# SAMV71_Xplained_Ultra_MCU_Peripherals.net
KiCad netlist of a schematic drawn in Altium Designer
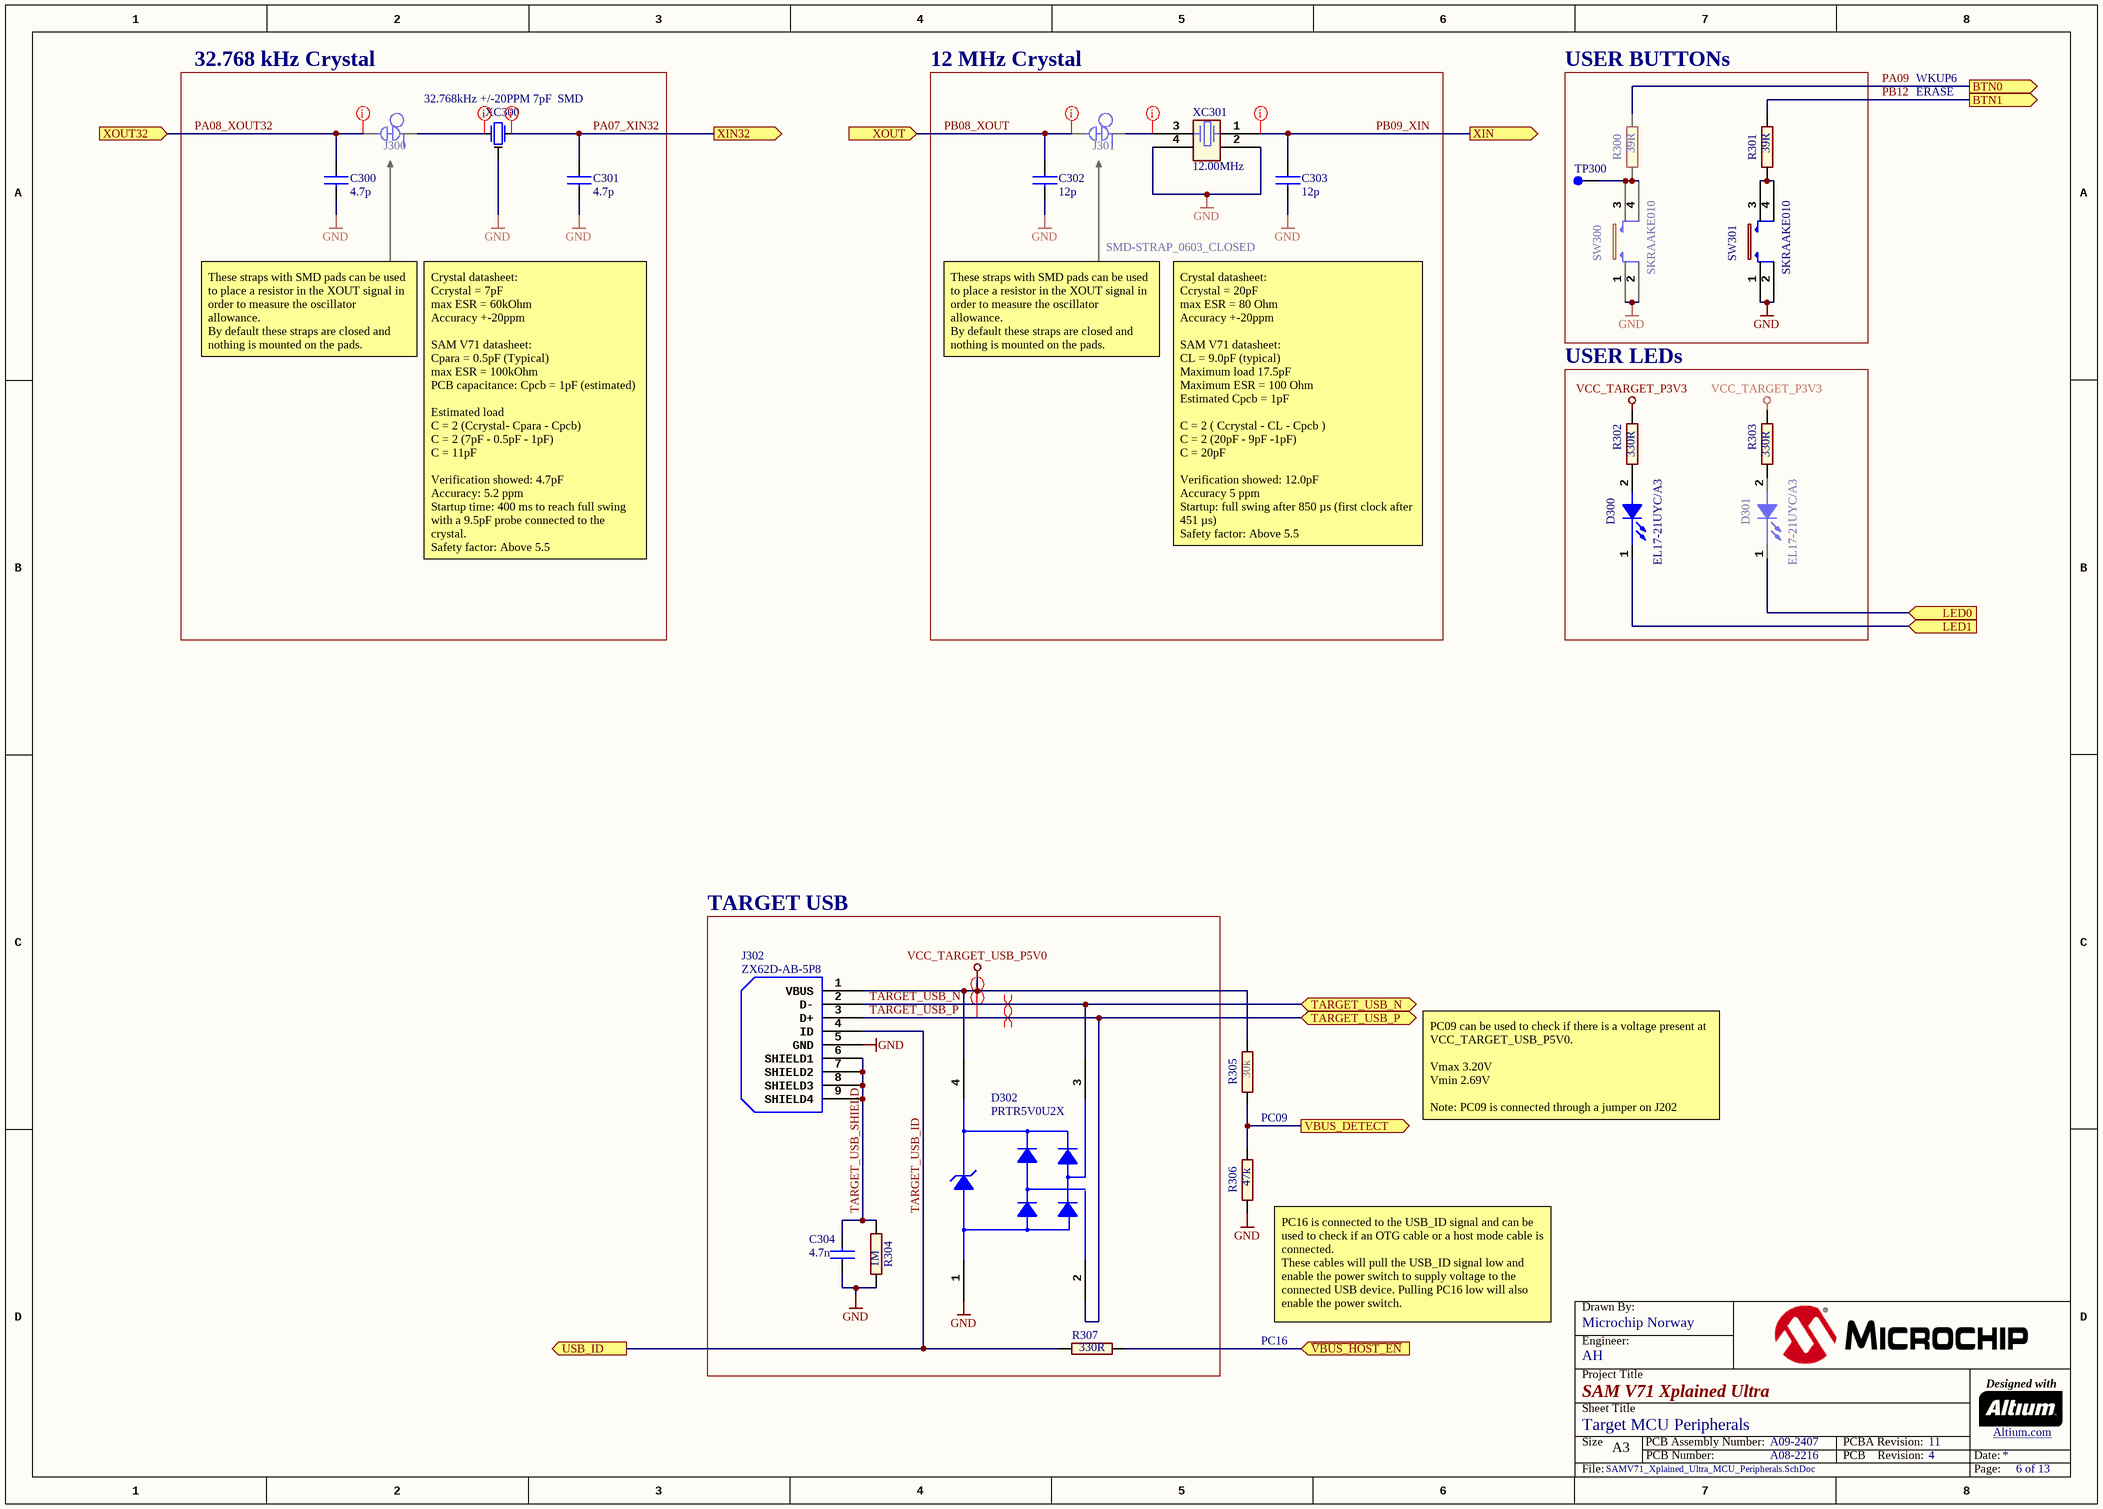
[diagram p0: SAMV71_Xplained_Ultra_MCU_Peripherals.SchDoc]

(export (version "E")
  (design (tool "Eeschema 10.0.6"))
  (components
    (comp (ref "C300")
      (value "4.7p")
      (footprint "AP1-00001")
      (description "Ceramic capacitor, SMD 0402, NP0, 50V, +/-0.25pF")
      (fields (field (name "TOLERANCE") "50V, +/-0.25pF") (field (name "MANUFACTURER") "YAGEO CORP"))
      (libsource (lib "AltiumDbLib") (part "CAP-NONPOL"))
    )
    (comp (ref "C301")
      (value "4.7p")
      (footprint "AP1-00001")
      (description "Ceramic capacitor, SMD 0402, NP0, 50V, +/-0.25pF")
      (fields (field (name "TOLERANCE") "50V, +/-0.25pF") (field (name "MANUFACTURER") "YAGEO CORP"))
      (libsource (lib "AltiumDbLib") (part "CAP-NONPOL"))
    )
    (comp (ref "C302")
      (value "12p")
      (footprint "AP1-00001")
      (description "Ceramic capacitor, SMD 0402, NP0, 50V, +/-5%")
      (fields (field (name "TOLERANCE") "50V, +/-5%") (field (name "MANUFACTURER") "Kemet"))
      (libsource (lib "AltiumDbLib") (part "CAP-NONPOL"))
    )
    (comp (ref "C303")
      (value "12p")
      (footprint "AP1-00001")
      (description "Ceramic capacitor, SMD 0402, NP0, 50V, +/-5%")
      (fields (field (name "TOLERANCE") "50V, +/-5%") (field (name "MANUFACTURER") "Kemet"))
      (libsource (lib "AltiumDbLib") (part "CAP-NONPOL"))
    )
    (comp (ref "C304")
      (value "4.7n")
      (footprint "AP1-00053")
      (description "Ceramic capacitor, SMD 0402, X7R, 25V, +/-10%")
      (fields (field (name "TOLERANCE") "25V, +/-10%") (field (name "MANUFACTURER") "PHYCOMP"))
      (libsource (lib "AltiumDbLib") (part "CAP-NONPOL"))
    )
    (comp (ref "D300")
      (value "EL17-21UYC/A3")
      (footprint "AP4-00013")
      (description "LED, Yellow, Wave length=591nm, SMD 0805, ±70°")
      (fields (field (name "MANUFACTURER") "Everlight") (field (name "MPN") "17-21UYC/S530-A3/TR8"))
      (libsource (lib "AltiumDbLib") (part "LED_12"))
    )
    (comp (ref "D301")
      (value "EL17-21UYC/A3")
      (footprint "AP4-00013")
      (description "LED, Yellow, Wave length=591nm, SMD 0805, ±70°")
      (fields (field (name "MANUFACTURER") "Everlight") (field (name "MPN") "17-21UYC/S530-A3/TR8"))
      (libsource (lib "AltiumDbLib") (part "LED_12"))
    )
    (comp (ref "D302")
      (value "PRTR5V0U2X")
      (footprint "AP4-00001")
      (description "Double rail-to-rail USB ESD protection diode")
      (fields (field (name "MANUFACTURER") "NXP"))
      (libsource (lib "AltiumDbLib") (part "PRTR5V0U2X"))
    )
    (comp (ref "J300")
      (value "~")
      (footprint "AP9-00044")
      (description "Default closed SMD strap, 0603 size")
      (libsource (lib "AltiumDbLib") (part "SMD-STRAP_CLOSED"))
    )
    (comp (ref "J301")
      (value "SMD-STRAP_0603_CLOSED")
      (footprint "AP9-00044")
      (description "Default closed SMD strap, 0603 size")
      (libsource (lib "AltiumDbLib") (part "SMD-STRAP_CLOSED"))
    )
    (comp (ref "J302")
      (value "ZX62D-AB-5P8")
      (footprint "AP8-00852")
      (description "Micro USB AB Connector, Standard SMT + DIP")
      (fields (field (name "MANUFACTURER") "HIROSE") (field (name "MPN") "ZX62D-AB-5P8(30)"))
      (libsource (lib "AltiumDbLib") (part "USB_AB"))
    )
    (comp (ref "R300")
      (value "39R")
      (footprint "AP2-00011")
      (description "Thick film resistor, SMD 0402, 1/16W, 1%")
      (fields (field (name "TOLERANCE") "1 %") (field (name "MANUFACTURER") "ASJ"))
      (libsource (lib "") (part "R2_1"))
    )
    (comp (ref "R301")
      (value "39R")
      (footprint "AP2-00011")
      (description "Thick film resistor, SMD 0402, 1/16W, 1%")
      (fields (field (name "TOLERANCE") "1 %") (field (name "MANUFACTURER") "ASJ"))
      (libsource (lib "") (part "R2_1"))
    )
    (comp (ref "R302")
      (value "330R")
      (footprint "AP2-00000")
      (description "Thick film resistor, SMD 0402, 1/16W, 1%")
      (fields (field (name "TOLERANCE") "1 %") (field (name "MANUFACTURER") "ASJ"))
      (libsource (lib "") (part "R2_2"))
    )
    (comp (ref "R303")
      (value "330R")
      (footprint "AP2-00000")
      (description "Thick film resistor, SMD 0402, 1/16W, 1%")
      (fields (field (name "TOLERANCE") "1 %") (field (name "MANUFACTURER") "ASJ"))
      (libsource (lib "") (part "R2_2"))
    )
    (comp (ref "R304")
      (value "1M")
      (footprint "AP2-00011")
      (description "Thick film resistor, SMD 0402, 1/16W, 1%")
      (fields (field (name "TOLERANCE") "1 %") (field (name "MANUFACTURER") "ASJ"))
      (libsource (lib "") (part "R2_1"))
    )
    (comp (ref "R305")
      (value "30k")
      (footprint "AP2-00000")
      (description "Thick film resistor, SMD 0402, 1/16W, 1%")
      (fields (field (name "TOLERANCE") "1 %") (field (name "MANUFACTURER") "ASJ"))
      (libsource (lib "") (part "R2_2"))
    )
    (comp (ref "R306")
      (value "47k")
      (footprint "AP2-00000")
      (description "Thick film resistor, SMD 0402, 1/16W, 1%")
      (fields (field (name "TOLERANCE") "1 %") (field (name "MANUFACTURER") "KOA"))
      (libsource (lib "") (part "R2_2"))
    )
    (comp (ref "R307")
      (value "330R")
      (footprint "AP2-00000")
      (description "Thick film resistor, SMD 0402, 1/16W, 1%")
      (fields (field (name "TOLERANCE") "1 %") (field (name "MANUFACTURER") "ASJ"))
      (libsource (lib "AltiumDbLib") (part "R2"))
    )
    (comp (ref "SW300")
      (value "SKRAAKE010")
      (footprint "AP8-00137")
      (description "6.2x6.2 mm SMD tact switch, same as A08-0091 but less force is needed")
      (fields
        (field (name "MANUFACTURER") "ALPS")
        (field (name "Comment") "same as A08-0091 but less force is needed; Can be ordered in low volumes from Mouser")
      )
      (libsource (lib "AltiumDbLib") (part "PUSHBUTTON1"))
    )
    (comp (ref "SW301")
      (value "SKRAAKE010")
      (footprint "AP8-00137")
      (description "6.2x6.2 mm SMD tact switch, same as A08-0091 but less force is needed")
      (fields
        (field (name "MANUFACTURER") "ALPS")
        (field (name "Comment") "same as A08-0091 but less force is needed; Can be ordered in low volumes from Mouser")
      )
      (libsource (lib "AltiumDbLib") (part "PUSHBUTTON1"))
    )
    (comp (ref "TP300")
      (value "~")
      (footprint "AP8-00010")
      (description "Single SMD testpad")
      (libsource (lib "AltiumDbLib") (part "TESTPOINT"))
    )
    (comp (ref "XC300")
      (value "32.768kHz +/-20PPM 7pF  SMD")
      (footprint "AP7-00044")
      (description "32k768 crystal, +-20ppm, CL=7pF, max ESR 60kOhm, SMD")
      (fields (field (name "TOLERANCE") "+/- 20 PPM") (field (name "MANUFACTURER") "Micro Crystal"))
      (libsource (lib "AltiumDbLib") (part "CRYSTAL_2P_metal"))
    )
    (comp (ref "XC301")
      (value "12.00MHz")
      (footprint "AP7-00039")
      (description "Fox FQ5032B 12.0MHz SMD crystal 738B-12")
      (fields (field (name "TOLERANCE") "Â±30ppm") (field (name "MANUFACTURER") "Fox  Electronics"))
      (libsource (lib "AltiumDbLib") (part "CRYSTAL1324"))
    )
  )
  (nets
    (net (code "1") (name "/LED0") (class "Default")
      (node (ref "D301") (pin "1") (pinfunction "CATHODE_1") (pintype "passive"))
    )
    (net (code "2") (name "/LED1") (class "Default")
      (node (ref "D300") (pin "1") (pinfunction "CATHODE_1") (pintype "passive"))
    )
    (net (code "3") (name "/PA07_XIN32") (class "Default")
      (node (ref "C301") (pin "1") (pinfunction "1_1") (pintype "passive"))
      (node (ref "XC300") (pin "2") (pinfunction "2_2") (pintype "passive"))
    )
    (net (code "4") (name "/PA08_XOUT32") (class "Default")
      (node (ref "C300") (pin "1") (pinfunction "1_1") (pintype "passive"))
      (node (ref "J300") (pin "2") (pinfunction "2_2") (pintype "passive"))
    )
    (net (code "5") (name "/PA09") (class "Default")
      (node (ref "R300") (pin "2") (pinfunction "2_2") (pintype "passive"))
    )
    (net (code "6") (name "/PB08_XOUT") (class "Default")
      (node (ref "C302") (pin "1") (pinfunction "1_1") (pintype "passive"))
      (node (ref "J301") (pin "2") (pinfunction "2_2") (pintype "passive"))
    )
    (net (code "7") (name "/PB09_XIN") (class "Default")
      (node (ref "C303") (pin "1") (pinfunction "1_1") (pintype "passive"))
      (node (ref "XC301") (pin "1") (pinfunction "1_1") (pintype "passive"))
    )
    (net (code "8") (name "/PB12") (class "Default")
      (node (ref "R301") (pin "2") (pinfunction "2_2") (pintype "passive"))
    )
    (net (code "9") (name "/TARGET_USB_ID") (class "Default")
      (node (ref "J302") (pin "4") (pinfunction "ID_4") (pintype "passive"))
      (node (ref "R307") (pin "1") (pinfunction "1_1") (pintype "passive"))
    )
    (net (code "10") (name "/TARGET_USB_N") (class "Default")
      (node (ref "D302") (pin "3") (pinfunction "I/O_2_3") (pintype "passive"))
      (node (ref "J302") (pin "2") (pinfunction "D-_2") (pintype "passive"))
    )
    (net (code "11") (name "/TARGET_USB_P") (class "Default")
      (node (ref "D302") (pin "2") (pinfunction "I/O_1_2") (pintype "passive"))
      (node (ref "J302") (pin "3") (pinfunction "D+_3") (pintype "passive"))
    )
    (net (code "12") (name "/TARGET_USB_SHIELD") (class "Default")
      (node (ref "C304") (pin "2") (pinfunction "2_2") (pintype "passive"))
      (node (ref "J302") (pin "6") (pinfunction "SHIELD1_6") (pintype "passive"))
      (node (ref "J302") (pin "7") (pinfunction "SHIELD2_7") (pintype "passive"))
      (node (ref "J302") (pin "8") (pinfunction "SHIELD3_8") (pintype "passive"))
      (node (ref "J302") (pin "9") (pinfunction "SHIELD4_9") (pintype "passive"))
      (node (ref "R304") (pin "2") (pinfunction "2_2") (pintype "passive"))
    )
    (net (code "13") (name "/VBUS_DETECT") (class "Default")
      (node (ref "R305") (pin "1") (pinfunction "1_1") (pintype "passive"))
      (node (ref "R306") (pin "2") (pinfunction "2_2") (pintype "passive"))
    )
    (net (code "14") (name "/~{VBUS_HOST_EN}") (class "Default")
      (node (ref "R307") (pin "2") (pinfunction "2_2") (pintype "passive"))
    )
    (net (code "15") (name "GND") (class "Default")
      (node (ref "C300") (pin "2") (pinfunction "2_2") (pintype "passive"))
      (node (ref "C301") (pin "2") (pinfunction "2_2") (pintype "passive"))
      (node (ref "C302") (pin "2") (pinfunction "2_2") (pintype "passive"))
      (node (ref "C303") (pin "2") (pinfunction "2_2") (pintype "passive"))
      (node (ref "C304") (pin "1") (pinfunction "1_1") (pintype "passive"))
      (node (ref "D302") (pin "1") (pinfunction "GND_1") (pintype "passive"))
      (node (ref "J302") (pin "5") (pinfunction "GND_5") (pintype "passive"))
      (node (ref "R304") (pin "1") (pinfunction "1_1") (pintype "passive"))
      (node (ref "R306") (pin "1") (pinfunction "1_1") (pintype "passive"))
      (node (ref "SW300") (pin "1") (pinfunction "1_1") (pintype "passive"))
      (node (ref "SW300") (pin "2") (pinfunction "2_2") (pintype "passive"))
      (node (ref "SW301") (pin "1") (pinfunction "1_1") (pintype "passive"))
      (node (ref "SW301") (pin "2") (pinfunction "2_2") (pintype "passive"))
      (node (ref "XC300") (pin "3") (pinfunction "3_3") (pintype "passive"))
      (node (ref "XC301") (pin "2") (pinfunction "2_2") (pintype "passive"))
      (node (ref "XC301") (pin "4") (pinfunction "4_4") (pintype "passive"))
    )
    (net (code "16") (name "Net-(D300-ANODE)") (class "Default")
      (node (ref "D300") (pin "2") (pinfunction "ANODE_2") (pintype "passive"))
      (node (ref "R302") (pin "1") (pinfunction "1_1") (pintype "passive"))
    )
    (net (code "17") (name "Net-(D301-ANODE)") (class "Default")
      (node (ref "D301") (pin "2") (pinfunction "ANODE_2") (pintype "passive"))
      (node (ref "R303") (pin "1") (pinfunction "1_1") (pintype "passive"))
    )
    (net (code "18") (name "Net-(J300-Pad1)") (class "Default")
      (node (ref "J300") (pin "1") (pinfunction "1_1") (pintype "passive"))
      (node (ref "XC300") (pin "1") (pinfunction "1_1") (pintype "passive"))
    )
    (net (code "19") (name "Net-(J301-Pad1)") (class "Default")
      (node (ref "J301") (pin "1") (pinfunction "1_1") (pintype "passive"))
      (node (ref "XC301") (pin "3") (pinfunction "3_3") (pintype "passive"))
    )
    (net (code "20") (name "Net-(R300-Pad1)") (class "Default")
      (node (ref "R300") (pin "1") (pinfunction "1_1") (pintype "passive"))
      (node (ref "SW300") (pin "3") (pinfunction "3_3") (pintype "passive"))
      (node (ref "SW300") (pin "4") (pinfunction "4_4") (pintype "passive"))
      (node (ref "TP300") (pin "1") (pinfunction "1_1") (pintype "passive"))
    )
    (net (code "21") (name "Net-(R301-Pad1)") (class "Default")
      (node (ref "R301") (pin "1") (pinfunction "1_1") (pintype "passive"))
      (node (ref "SW301") (pin "3") (pinfunction "3_3") (pintype "passive"))
      (node (ref "SW301") (pin "4") (pinfunction "4_4") (pintype "passive"))
    )
    (net (code "22") (name "VCC_TARGET_P3V3") (class "Default")
      (node (ref "R302") (pin "2") (pinfunction "2_2") (pintype "passive"))
      (node (ref "R303") (pin "2") (pinfunction "2_2") (pintype "passive"))
    )
    (net (code "23") (name "VCC_TARGET_USB_P5V0") (class "Default")
      (node (ref "D302") (pin "4") (pinfunction "VCC_4") (pintype "passive"))
      (node (ref "J302") (pin "1") (pinfunction "VBUS_1") (pintype "passive"))
      (node (ref "R305") (pin "2") (pinfunction "2_2") (pintype "passive"))
    )
  )
)
